# Sheet6.net
KiCad netlist of a schematic drawn in Altium Designer
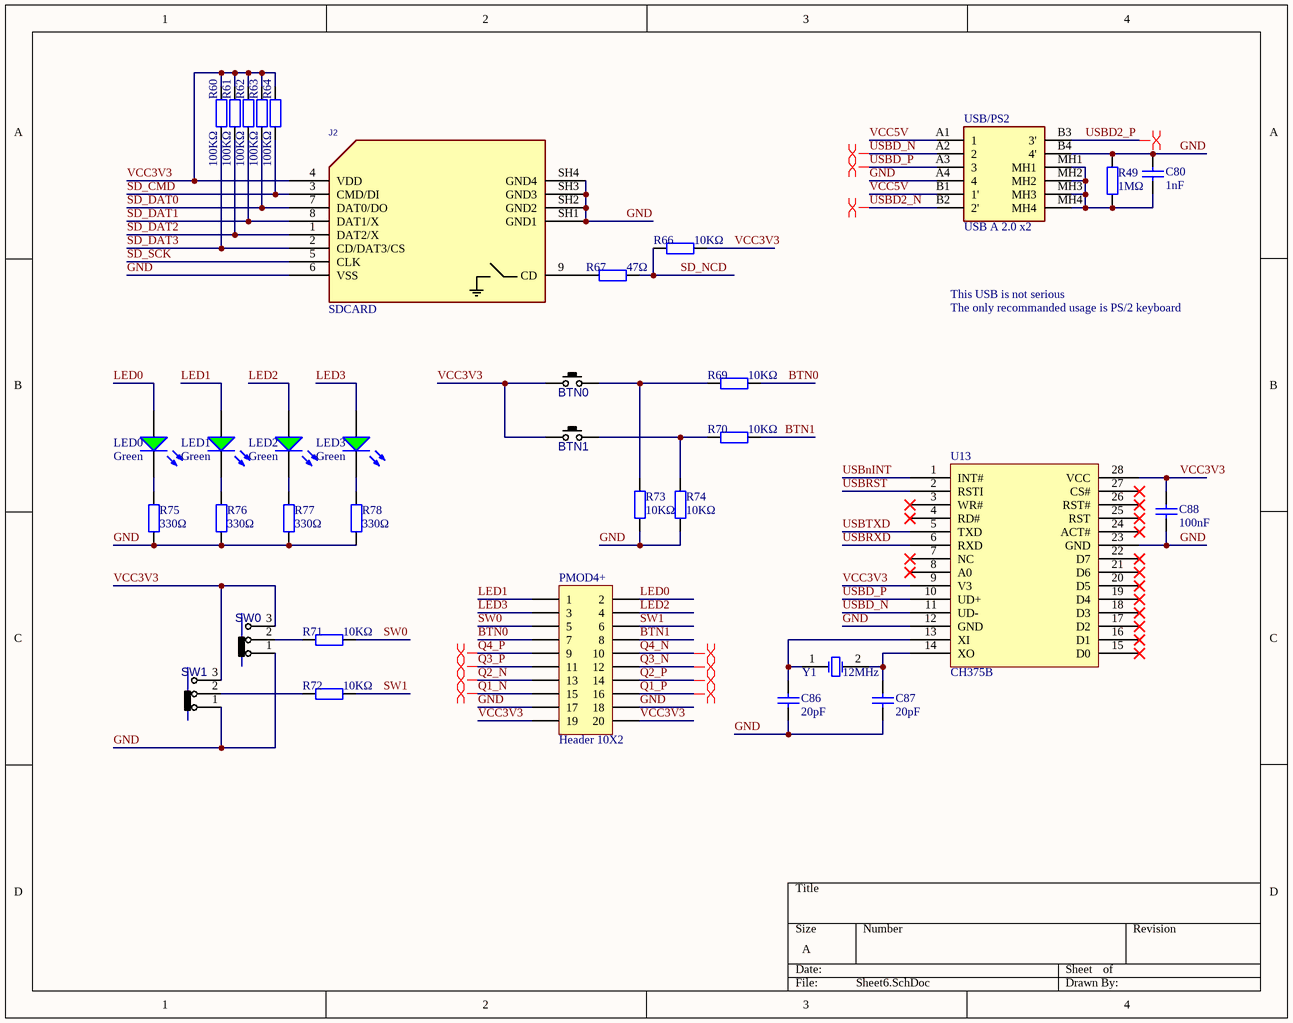
[diagram p0: Sheet6.SchDoc]

(export (version "E")
  (design (tool "Eeschema 10.0.6"))
  (components
    (comp (ref "BTN0")
      (value "PUSHBUTTON")
      (footprint "SWPBS_SPST_6X3X5")
      (description "SWITCH, PUSH BUTTON, TACTILE, SMD, SPST, 6X3.5X4.3mm")
      (fields (field (name "MANF") "Panasonic") (field (name "MANF_P#") "EVQ-PNF04M"))
      (libsource (lib "Switch Push Botton") (part "SWPBS_SPST_6X3X4"))
    )
    (comp (ref "BTN1")
      (value "PUSHBUTTON")
      (footprint "SWPBS_SPST_6X3X5")
      (description "SWITCH, PUSH BUTTON, TACTILE, SMD, SPST, 6X3.5X4.3mm")
      (fields (field (name "MANF") "Panasonic") (field (name "MANF_P#") "EVQ-PNF04M"))
      (libsource (lib "Switch Push Botton") (part "SWPBS_SPST_6X3X4"))
    )
    (comp (ref "C80")
      (value "1nF")
      (footprint "0805_C")
      (description "贴片电容")
      (libsource (lib "Cap") (part "0805 1nF (102) 10% 50V"))
    )
    (comp (ref "C86")
      (value "20pF")
      (footprint "0805_C")
      (description "贴片电容")
      (libsource (lib "Cap") (part "0805 20pF (200) 5% 50V"))
    )
    (comp (ref "C87")
      (value "20pF")
      (footprint "0805_C")
      (description "贴片电容")
      (libsource (lib "Cap") (part "0805 20pF (200) 5% 50V"))
    )
    (comp (ref "C88")
      (value "100nF")
      (footprint "1206_C")
      (description "贴片电容")
      (libsource (lib "Cap") (part "1206 100nF (104) 10% 50V"))
    )
    (comp (ref "J2")
      (value "SDCARD")
      (footprint "SDMICRO_AT")
      (description "SD MICRO exist in Iran, Attend 112J-TDAR-R01")
      (fields (field (name "MANF") "Attend") (field (name "MANF_P#") "112J-TDAR-R01"))
      (libsource (lib "Connector Micro SD") (part "SOCKET_SDMICRO_AT"))
    )
    (comp (ref "LED0")
      (value "Green")
      (footprint "0805_LED_S1")
      (description "发光二极管")
      (libsource (lib "LED") (part "0805 翠绿"))
    )
    (comp (ref "LED1")
      (value "Green")
      (footprint "0805_LED_S1")
      (description "发光二极管")
      (libsource (lib "LED") (part "0805 翠绿"))
    )
    (comp (ref "LED2")
      (value "Green")
      (footprint "0805_LED_S1")
      (description "发光二极管")
      (libsource (lib "LED") (part "0805 翠绿"))
    )
    (comp (ref "LED3")
      (value "Green")
      (footprint "0805_LED_S1")
      (description "发光二极管")
      (libsource (lib "LED") (part "0805 翠绿"))
    )
    (comp (ref "PMOD4+")
      (value "Header 10X2")
      (footprint "HDR2X10")
      (description "Header, 10-Pin, Dual row")
      (fields (field (name "PUBLISHER") "Altium Limited"))
      (libsource (lib "Miscellaneous Connectors") (part "Header 10X2"))
    )
    (comp (ref "R49")
      (value "1MΩ")
      (footprint "0805_R")
      (description "贴片电阻")
      (libsource (lib "RES") (part "0805 1MΩ (1004) 1%"))
    )
    (comp (ref "R60")
      (value "100KΩ")
      (footprint "1206_R")
      (description "贴片电阻")
      (libsource (lib "RES") (part "1206 100KΩ (1003) 1%"))
    )
    (comp (ref "R61")
      (value "100KΩ")
      (footprint "1206_R")
      (description "贴片电阻")
      (libsource (lib "RES") (part "1206 100KΩ (1003) 1%"))
    )
    (comp (ref "R62")
      (value "100KΩ")
      (footprint "1206_R")
      (description "贴片电阻")
      (libsource (lib "RES") (part "1206 100KΩ (1003) 1%"))
    )
    (comp (ref "R63")
      (value "100KΩ")
      (footprint "1206_R")
      (description "贴片电阻")
      (libsource (lib "RES") (part "1206 100KΩ (1003) 1%"))
    )
    (comp (ref "R64")
      (value "100KΩ")
      (footprint "1206_R")
      (description "贴片电阻")
      (libsource (lib "RES") (part "1206 100KΩ (1003) 1%"))
    )
    (comp (ref "R66")
      (value "10KΩ")
      (footprint "1206_R")
      (description "贴片电阻")
      (libsource (lib "") (part "1206 10KΩ (1002) 1%_1"))
    )
    (comp (ref "R67")
      (value "47Ω")
      (footprint "0805_R")
      (description "贴片电阻")
      (libsource (lib "RES") (part "0805 47Ω (47R0) 1%"))
    )
    (comp (ref "R69")
      (value "10KΩ")
      (footprint "1206_R")
      (description "贴片电阻")
      (libsource (lib "") (part "1206 10KΩ (1002) 1%_1"))
    )
    (comp (ref "R70")
      (value "10KΩ")
      (footprint "1206_R")
      (description "贴片电阻")
      (libsource (lib "") (part "1206 10KΩ (1002) 1%_1"))
    )
    (comp (ref "R71")
      (value "10KΩ")
      (footprint "1206_R")
      (description "贴片电阻")
      (libsource (lib "") (part "1206 10KΩ (1002) 1%_1"))
    )
    (comp (ref "R72")
      (value "10KΩ")
      (footprint "1206_R")
      (description "贴片电阻")
      (libsource (lib "") (part "1206 10KΩ (1002) 1%_1"))
    )
    (comp (ref "R73")
      (value "10KΩ")
      (footprint "1206_R")
      (description "贴片电阻")
      (libsource (lib "RES") (part "1206 10KΩ (1002) 1%"))
    )
    (comp (ref "R74")
      (value "10KΩ")
      (footprint "1206_R")
      (description "贴片电阻")
      (libsource (lib "RES") (part "1206 10KΩ (1002) 1%"))
    )
    (comp (ref "R75")
      (value "330Ω")
      (footprint "0805_R")
      (description "贴片电阻")
      (libsource (lib "RES") (part "0805 330Ω (3300) 1%"))
    )
    (comp (ref "R76")
      (value "330Ω")
      (footprint "0805_R")
      (description "贴片电阻")
      (libsource (lib "RES") (part "0805 330Ω (3300) 1%"))
    )
    (comp (ref "R77")
      (value "330Ω")
      (footprint "0805_R")
      (description "贴片电阻")
      (libsource (lib "RES") (part "0805 330Ω (3300) 1%"))
    )
    (comp (ref "R78")
      (value "330Ω")
      (footprint "0805_R")
      (description "贴片电阻")
      (libsource (lib "RES") (part "0805 330Ω (3300) 1%"))
    )
    (comp (ref "SW0")
      (value "SlideSwitch")
      (footprint "SWSLIDT_SPDT_S_8X4")
      (description "SWITCH, SLIDE, SPDT, 8.6X4.3mm, THD")
      (fields (field (name "MANF") "C&K") (field (name "MANF_PART#") "OS102011MS2QN1"))
      (libsource (lib "Switch Slide") (part "SWSLIDT_SPDT_S_8X4"))
    )
    (comp (ref "SW1")
      (value "SlideSwitch")
      (footprint "SWSLIDT_SPDT_S_8X4")
      (description "SWITCH, SLIDE, SPDT, 8.6X4.3mm, THD")
      (fields (field (name "MANF") "C&K") (field (name "MANF_PART#") "OS102011MS2QN1"))
      (libsource (lib "Switch Slide") (part "SWSLIDT_SPDT_S_8X4"))
    )
    (comp (ref "U13")
      (value "CH375B")
      (footprint "SOIC-28_300mil")
      (description "USB")
      (libsource (lib "IC") (part "CH376S_[C14166]"))
    )
    (comp (ref "USB/PS2")
      (value "USB A 2.0 x2")
      (footprint "SamacSys:0672983090")
      (description "Connector")
      (fields (field (name "MANUFACTURER_PART_NUMBER") "0672983090"))
      (libsource (lib "*") (part "0672983090"))
    )
    (comp (ref "Y1")
      (value "12MHz")
      (footprint "SMD-5032_2P")
      (description "贴片晶振")
      (libsource (lib "CrystalOscillator") (part "SMD-5032_2P 11.0592MHZ 20PF 20PPM"))
    )
  )
  (nets
    (net (code "1") (name "/BTN0") (class "Default")
      (node (ref "PMOD4+") (pin "7") (pinfunction "7_7") (pintype "passive"))
      (node (ref "R69") (pin "2") (pinfunction "2_2") (pintype "passive"))
    )
    (net (code "2") (name "/BTN1") (class "Default")
      (node (ref "PMOD4+") (pin "8") (pinfunction "8_8") (pintype "passive"))
      (node (ref "R70") (pin "2") (pinfunction "2_2") (pintype "passive"))
    )
    (net (code "3") (name "/GND") (class "Default")
      (node (ref "C80") (pin "1") (pinfunction "1_1") (pintype "passive"))
      (node (ref "C86") (pin "1") (pinfunction "1_1") (pintype "passive"))
      (node (ref "C87") (pin "1") (pinfunction "1_1") (pintype "passive"))
      (node (ref "C88") (pin "1") (pinfunction "1_1") (pintype "passive"))
      (node (ref "J2") (pin "6") (pinfunction "VSS_6") (pintype "passive"))
      (node (ref "J2") (pin "SH1") (pinfunction "GND1_SH1") (pintype "passive"))
      (node (ref "J2") (pin "SH2") (pinfunction "GND2_SH2") (pintype "passive"))
      (node (ref "J2") (pin "SH3") (pinfunction "GND3_SH3") (pintype "passive"))
      (node (ref "J2") (pin "SH4") (pinfunction "GND4_SH4") (pintype "passive"))
      (node (ref "PMOD4+") (pin "17") (pinfunction "17_17") (pintype "passive"))
      (node (ref "PMOD4+") (pin "18") (pinfunction "18_18") (pintype "passive"))
      (node (ref "R49") (pin "1") (pinfunction "1_1") (pintype "passive"))
      (node (ref "R73") (pin "1") (pinfunction "1_1") (pintype "passive"))
      (node (ref "R74") (pin "1") (pinfunction "1_1") (pintype "passive"))
      (node (ref "R75") (pin "1") (pinfunction "1_1") (pintype "passive"))
      (node (ref "R76") (pin "1") (pinfunction "1_1") (pintype "passive"))
      (node (ref "R77") (pin "1") (pinfunction "1_1") (pintype "passive"))
      (node (ref "R78") (pin "1") (pinfunction "1_1") (pintype "passive"))
      (node (ref "SW0") (pin "1") (pinfunction "P1_1") (pintype "passive"))
      (node (ref "SW1") (pin "1") (pinfunction "P1_1") (pintype "passive"))
      (node (ref "U13") (pin "12") (pinfunction "GND_12") (pintype "passive"))
      (node (ref "U13") (pin "23") (pinfunction "GND_23") (pintype "passive"))
      (node (ref "USB/PS2") (pin "A4") (pinfunction "4_A4") (pintype "passive"))
      (node (ref "USB/PS2") (pin "B4") (pinfunction "4'_B4") (pintype "passive"))
    )
    (net (code "4") (name "/LED0") (class "Default")
      (node (ref "LED0") (pin "A") (pinfunction "A_A") (pintype "passive"))
      (node (ref "PMOD4+") (pin "2") (pinfunction "2_2") (pintype "passive"))
    )
    (net (code "5") (name "/LED1") (class "Default")
      (node (ref "LED1") (pin "A") (pinfunction "A_A") (pintype "passive"))
      (node (ref "PMOD4+") (pin "1") (pinfunction "1_1") (pintype "passive"))
    )
    (net (code "6") (name "/LED2") (class "Default")
      (node (ref "LED2") (pin "A") (pinfunction "A_A") (pintype "passive"))
      (node (ref "PMOD4+") (pin "4") (pinfunction "4_4") (pintype "passive"))
    )
    (net (code "7") (name "/LED3") (class "Default")
      (node (ref "LED3") (pin "A") (pinfunction "A_A") (pintype "passive"))
      (node (ref "PMOD4+") (pin "3") (pinfunction "3_3") (pintype "passive"))
    )
    (net (code "8") (name "/Q1_N") (class "Default")
      (node (ref "PMOD4+") (pin "15") (pinfunction "15_15") (pintype "passive"))
    )
    (net (code "9") (name "/Q1_P") (class "Default")
      (node (ref "PMOD4+") (pin "16") (pinfunction "16_16") (pintype "passive"))
    )
    (net (code "10") (name "/Q2_N") (class "Default")
      (node (ref "PMOD4+") (pin "13") (pinfunction "13_13") (pintype "passive"))
    )
    (net (code "11") (name "/Q2_P") (class "Default")
      (node (ref "PMOD4+") (pin "14") (pinfunction "14_14") (pintype "passive"))
    )
    (net (code "12") (name "/Q3_N") (class "Default")
      (node (ref "PMOD4+") (pin "12") (pinfunction "12_12") (pintype "passive"))
    )
    (net (code "13") (name "/Q3_P") (class "Default")
      (node (ref "PMOD4+") (pin "11") (pinfunction "11_11") (pintype "passive"))
    )
    (net (code "14") (name "/Q4_N") (class "Default")
      (node (ref "PMOD4+") (pin "10") (pinfunction "10_10") (pintype "passive"))
    )
    (net (code "15") (name "/Q4_P") (class "Default")
      (node (ref "PMOD4+") (pin "9") (pinfunction "9_9") (pintype "passive"))
    )
    (net (code "16") (name "/SD_CMD") (class "Default")
      (node (ref "J2") (pin "3") (pinfunction "CMD/DI_3") (pintype "passive"))
      (node (ref "R64") (pin "1") (pinfunction "1_1") (pintype "passive"))
    )
    (net (code "17") (name "/SD_DAT0") (class "Default")
      (node (ref "J2") (pin "7") (pinfunction "DAT0/DO_7") (pintype "passive"))
      (node (ref "R63") (pin "1") (pinfunction "1_1") (pintype "passive"))
    )
    (net (code "18") (name "/SD_DAT1") (class "Default")
      (node (ref "J2") (pin "8") (pinfunction "DAT1/X_8") (pintype "passive"))
      (node (ref "R62") (pin "1") (pinfunction "1_1") (pintype "passive"))
    )
    (net (code "19") (name "/SD_DAT2") (class "Default")
      (node (ref "J2") (pin "1") (pinfunction "DAT2/X_1") (pintype "passive"))
      (node (ref "R61") (pin "1") (pinfunction "1_1") (pintype "passive"))
    )
    (net (code "20") (name "/SD_DAT3") (class "Default")
      (node (ref "J2") (pin "2") (pinfunction "CD/DAT3/CS_2") (pintype "passive"))
      (node (ref "R60") (pin "1") (pinfunction "1_1") (pintype "passive"))
    )
    (net (code "21") (name "/SD_NCD") (class "Default")
      (node (ref "R66") (pin "1") (pinfunction "1_1") (pintype "passive"))
      (node (ref "R67") (pin "2") (pinfunction "2_2") (pintype "passive"))
    )
    (net (code "22") (name "/SD_SCK") (class "Default")
      (node (ref "J2") (pin "5") (pinfunction "CLK_5") (pintype "passive"))
    )
    (net (code "23") (name "/SW0") (class "Default")
      (node (ref "PMOD4+") (pin "5") (pinfunction "5_5") (pintype "passive"))
      (node (ref "R71") (pin "2") (pinfunction "2_2") (pintype "passive"))
    )
    (net (code "24") (name "/SW1") (class "Default")
      (node (ref "PMOD4+") (pin "6") (pinfunction "6_6") (pintype "passive"))
      (node (ref "R72") (pin "2") (pinfunction "2_2") (pintype "passive"))
    )
    (net (code "25") (name "/USBD2_N") (class "Default")
      (node (ref "USB/PS2") (pin "B2") (pinfunction "2'_B2") (pintype "passive"))
    )
    (net (code "26") (name "/USBD2_P") (class "Default")
      (node (ref "USB/PS2") (pin "B3") (pinfunction "3'_B3") (pintype "passive"))
    )
    (net (code "27") (name "/USBD_N") (class "Default")
      (node (ref "U13") (pin "11") (pinfunction "UD-_11") (pintype "passive"))
      (node (ref "USB/PS2") (pin "A2") (pinfunction "2_A2") (pintype "passive"))
    )
    (net (code "28") (name "/USBD_P") (class "Default")
      (node (ref "U13") (pin "10") (pinfunction "UD+_10") (pintype "passive"))
      (node (ref "USB/PS2") (pin "A3") (pinfunction "3_A3") (pintype "passive"))
    )
    (net (code "29") (name "/USBRST") (class "Default")
      (node (ref "U13") (pin "2") (pinfunction "RSTI_2") (pintype "passive"))
    )
    (net (code "30") (name "/USBRXD") (class "Default")
      (node (ref "U13") (pin "6") (pinfunction "RXD_6") (pintype "passive"))
    )
    (net (code "31") (name "/USBTXD") (class "Default")
      (node (ref "U13") (pin "5") (pinfunction "TXD_5") (pintype "passive"))
    )
    (net (code "32") (name "/USBnINT") (class "Default")
      (node (ref "U13") (pin "1") (pinfunction "INT#_1") (pintype "passive"))
    )
    (net (code "33") (name "/VCC3V3") (class "Default")
      (node (ref "BTN0") (pin "1") (pinfunction "P1_1") (pintype "passive"))
      (node (ref "BTN1") (pin "1") (pinfunction "P1_1") (pintype "passive"))
      (node (ref "C88") (pin "2") (pinfunction "2_2") (pintype "passive"))
      (node (ref "J2") (pin "4") (pinfunction "VDD_4") (pintype "passive"))
      (node (ref "PMOD4+") (pin "19") (pinfunction "19_19") (pintype "passive"))
      (node (ref "PMOD4+") (pin "20") (pinfunction "20_20") (pintype "passive"))
      (node (ref "R60") (pin "2") (pinfunction "2_2") (pintype "passive"))
      (node (ref "R61") (pin "2") (pinfunction "2_2") (pintype "passive"))
      (node (ref "R62") (pin "2") (pinfunction "2_2") (pintype "passive"))
      (node (ref "R63") (pin "2") (pinfunction "2_2") (pintype "passive"))
      (node (ref "R64") (pin "2") (pinfunction "2_2") (pintype "passive"))
      (node (ref "R66") (pin "2") (pinfunction "2_2") (pintype "passive"))
      (node (ref "SW0") (pin "3") (pinfunction "P4_3") (pintype "passive"))
      (node (ref "SW1") (pin "3") (pinfunction "P4_3") (pintype "passive"))
      (node (ref "U13") (pin "28") (pinfunction "VCC_28") (pintype "passive"))
      (node (ref "U13") (pin "9") (pinfunction "V3_9") (pintype "passive"))
    )
    (net (code "34") (name "/VCC5V") (class "Default")
      (node (ref "USB/PS2") (pin "A1") (pinfunction "1_A1") (pintype "passive"))
      (node (ref "USB/PS2") (pin "B1") (pinfunction "1'_B1") (pintype "passive"))
    )
    (net (code "35") (name "Net-(BTN0-P3)") (class "Default")
      (node (ref "BTN0") (pin "2") (pinfunction "P3_2") (pintype "passive"))
      (node (ref "R69") (pin "1") (pinfunction "1_1") (pintype "passive"))
      (node (ref "R73") (pin "2") (pinfunction "2_2") (pintype "passive"))
    )
    (net (code "36") (name "Net-(BTN1-P3)") (class "Default")
      (node (ref "BTN1") (pin "2") (pinfunction "P3_2") (pintype "passive"))
      (node (ref "R70") (pin "1") (pinfunction "1_1") (pintype "passive"))
      (node (ref "R74") (pin "2") (pinfunction "2_2") (pintype "passive"))
    )
    (net (code "37") (name "Net-(C80-Pad2)") (class "Default")
      (node (ref "C80") (pin "2") (pinfunction "2_2") (pintype "passive"))
      (node (ref "R49") (pin "2") (pinfunction "2_2") (pintype "passive"))
      (node (ref "USB/PS2") (pin "MH1") (pinfunction "MH1_MH1") (pintype "passive"))
      (node (ref "USB/PS2") (pin "MH2") (pinfunction "MH2_MH2") (pintype "passive"))
      (node (ref "USB/PS2") (pin "MH3") (pinfunction "MH3_MH3") (pintype "passive"))
      (node (ref "USB/PS2") (pin "MH4") (pinfunction "MH4_MH4") (pintype "passive"))
    )
    (net (code "38") (name "Net-(J2-CD)") (class "Default")
      (node (ref "J2") (pin "9") (pinfunction "CD_9") (pintype "passive"))
      (node (ref "R67") (pin "1") (pinfunction "1_1") (pintype "passive"))
    )
    (net (code "39") (name "Net-(LED0-PadK)") (class "Default")
      (node (ref "LED0") (pin "K") (pinfunction "K_K") (pintype "passive"))
      (node (ref "R75") (pin "2") (pinfunction "2_2") (pintype "passive"))
    )
    (net (code "40") (name "Net-(LED1-PadK)") (class "Default")
      (node (ref "LED1") (pin "K") (pinfunction "K_K") (pintype "passive"))
      (node (ref "R76") (pin "2") (pinfunction "2_2") (pintype "passive"))
    )
    (net (code "41") (name "Net-(LED2-PadK)") (class "Default")
      (node (ref "LED2") (pin "K") (pinfunction "K_K") (pintype "passive"))
      (node (ref "R77") (pin "2") (pinfunction "2_2") (pintype "passive"))
    )
    (net (code "42") (name "Net-(LED3-PadK)") (class "Default")
      (node (ref "LED3") (pin "K") (pinfunction "K_K") (pintype "passive"))
      (node (ref "R78") (pin "2") (pinfunction "2_2") (pintype "passive"))
    )
    (net (code "43") (name "Net-(SW0-P3)") (class "Default")
      (node (ref "R71") (pin "1") (pinfunction "1_1") (pintype "passive"))
      (node (ref "SW0") (pin "2") (pinfunction "P3_2") (pintype "passive"))
    )
    (net (code "44") (name "Net-(SW1-P3)") (class "Default")
      (node (ref "R72") (pin "1") (pinfunction "1_1") (pintype "passive"))
      (node (ref "SW1") (pin "2") (pinfunction "P3_2") (pintype "passive"))
    )
    (net (code "45") (name "Net-(U13-XI)") (class "Default")
      (node (ref "C86") (pin "2") (pinfunction "2_2") (pintype "passive"))
      (node (ref "U13") (pin "13") (pinfunction "XI_13") (pintype "passive"))
      (node (ref "Y1") (pin "1") (pinfunction "OSC1_1") (pintype "passive"))
    )
    (net (code "46") (name "Net-(U13-XO)") (class "Default")
      (node (ref "C87") (pin "2") (pinfunction "2_2") (pintype "passive"))
      (node (ref "U13") (pin "14") (pinfunction "XO_14") (pintype "passive"))
      (node (ref "Y1") (pin "2") (pinfunction "OSC2_2") (pintype "passive"))
    )
    (net (code "47") (name "unconnected-(U13-A0-Pad8)") (class "Default")
      (node (ref "U13") (pin "8") (pinfunction "A0_8") (pintype "passive+no_connect"))
    )
    (net (code "48") (name "unconnected-(U13-ACT#-Pad24)") (class "Default")
      (node (ref "U13") (pin "24") (pinfunction "ACT#_24") (pintype "passive+no_connect"))
    )
    (net (code "49") (name "unconnected-(U13-CS#-Pad27)") (class "Default")
      (node (ref "U13") (pin "27") (pinfunction "CS#_27") (pintype "passive+no_connect"))
    )
    (net (code "50") (name "unconnected-(U13-D0-Pad15)") (class "Default")
      (node (ref "U13") (pin "15") (pinfunction "D0_15") (pintype "passive+no_connect"))
    )
    (net (code "51") (name "unconnected-(U13-D1-Pad16)") (class "Default")
      (node (ref "U13") (pin "16") (pinfunction "D1_16") (pintype "passive+no_connect"))
    )
    (net (code "52") (name "unconnected-(U13-D2-Pad17)") (class "Default")
      (node (ref "U13") (pin "17") (pinfunction "D2_17") (pintype "passive+no_connect"))
    )
    (net (code "53") (name "unconnected-(U13-D3-Pad18)") (class "Default")
      (node (ref "U13") (pin "18") (pinfunction "D3_18") (pintype "passive+no_connect"))
    )
    (net (code "54") (name "unconnected-(U13-D4-Pad19)") (class "Default")
      (node (ref "U13") (pin "19") (pinfunction "D4_19") (pintype "passive+no_connect"))
    )
    (net (code "55") (name "unconnected-(U13-D5-Pad20)") (class "Default")
      (node (ref "U13") (pin "20") (pinfunction "D5_20") (pintype "passive+no_connect"))
    )
    (net (code "56") (name "unconnected-(U13-D6-Pad21)") (class "Default")
      (node (ref "U13") (pin "21") (pinfunction "D6_21") (pintype "passive+no_connect"))
    )
    (net (code "57") (name "unconnected-(U13-D7-Pad22)") (class "Default")
      (node (ref "U13") (pin "22") (pinfunction "D7_22") (pintype "passive+no_connect"))
    )
    (net (code "58") (name "unconnected-(U13-NC-Pad7)") (class "Default")
      (node (ref "U13") (pin "7") (pinfunction "NC_7") (pintype "passive+no_connect"))
    )
    (net (code "59") (name "unconnected-(U13-RD#-Pad4)") (class "Default")
      (node (ref "U13") (pin "4") (pinfunction "RD#_4") (pintype "passive+no_connect"))
    )
    (net (code "60") (name "unconnected-(U13-RST#-Pad26)") (class "Default")
      (node (ref "U13") (pin "26") (pinfunction "RST#_26") (pintype "passive+no_connect"))
    )
    (net (code "61") (name "unconnected-(U13-RST-Pad25)") (class "Default")
      (node (ref "U13") (pin "25") (pinfunction "RST_25") (pintype "passive+no_connect"))
    )
    (net (code "62") (name "unconnected-(U13-WR#-Pad3)") (class "Default")
      (node (ref "U13") (pin "3") (pinfunction "WR#_3") (pintype "passive+no_connect"))
    )
  )
)
